# LMN_Danger_Shield-v18.net
KiCad netlist of a schematic drawn in EAGLE
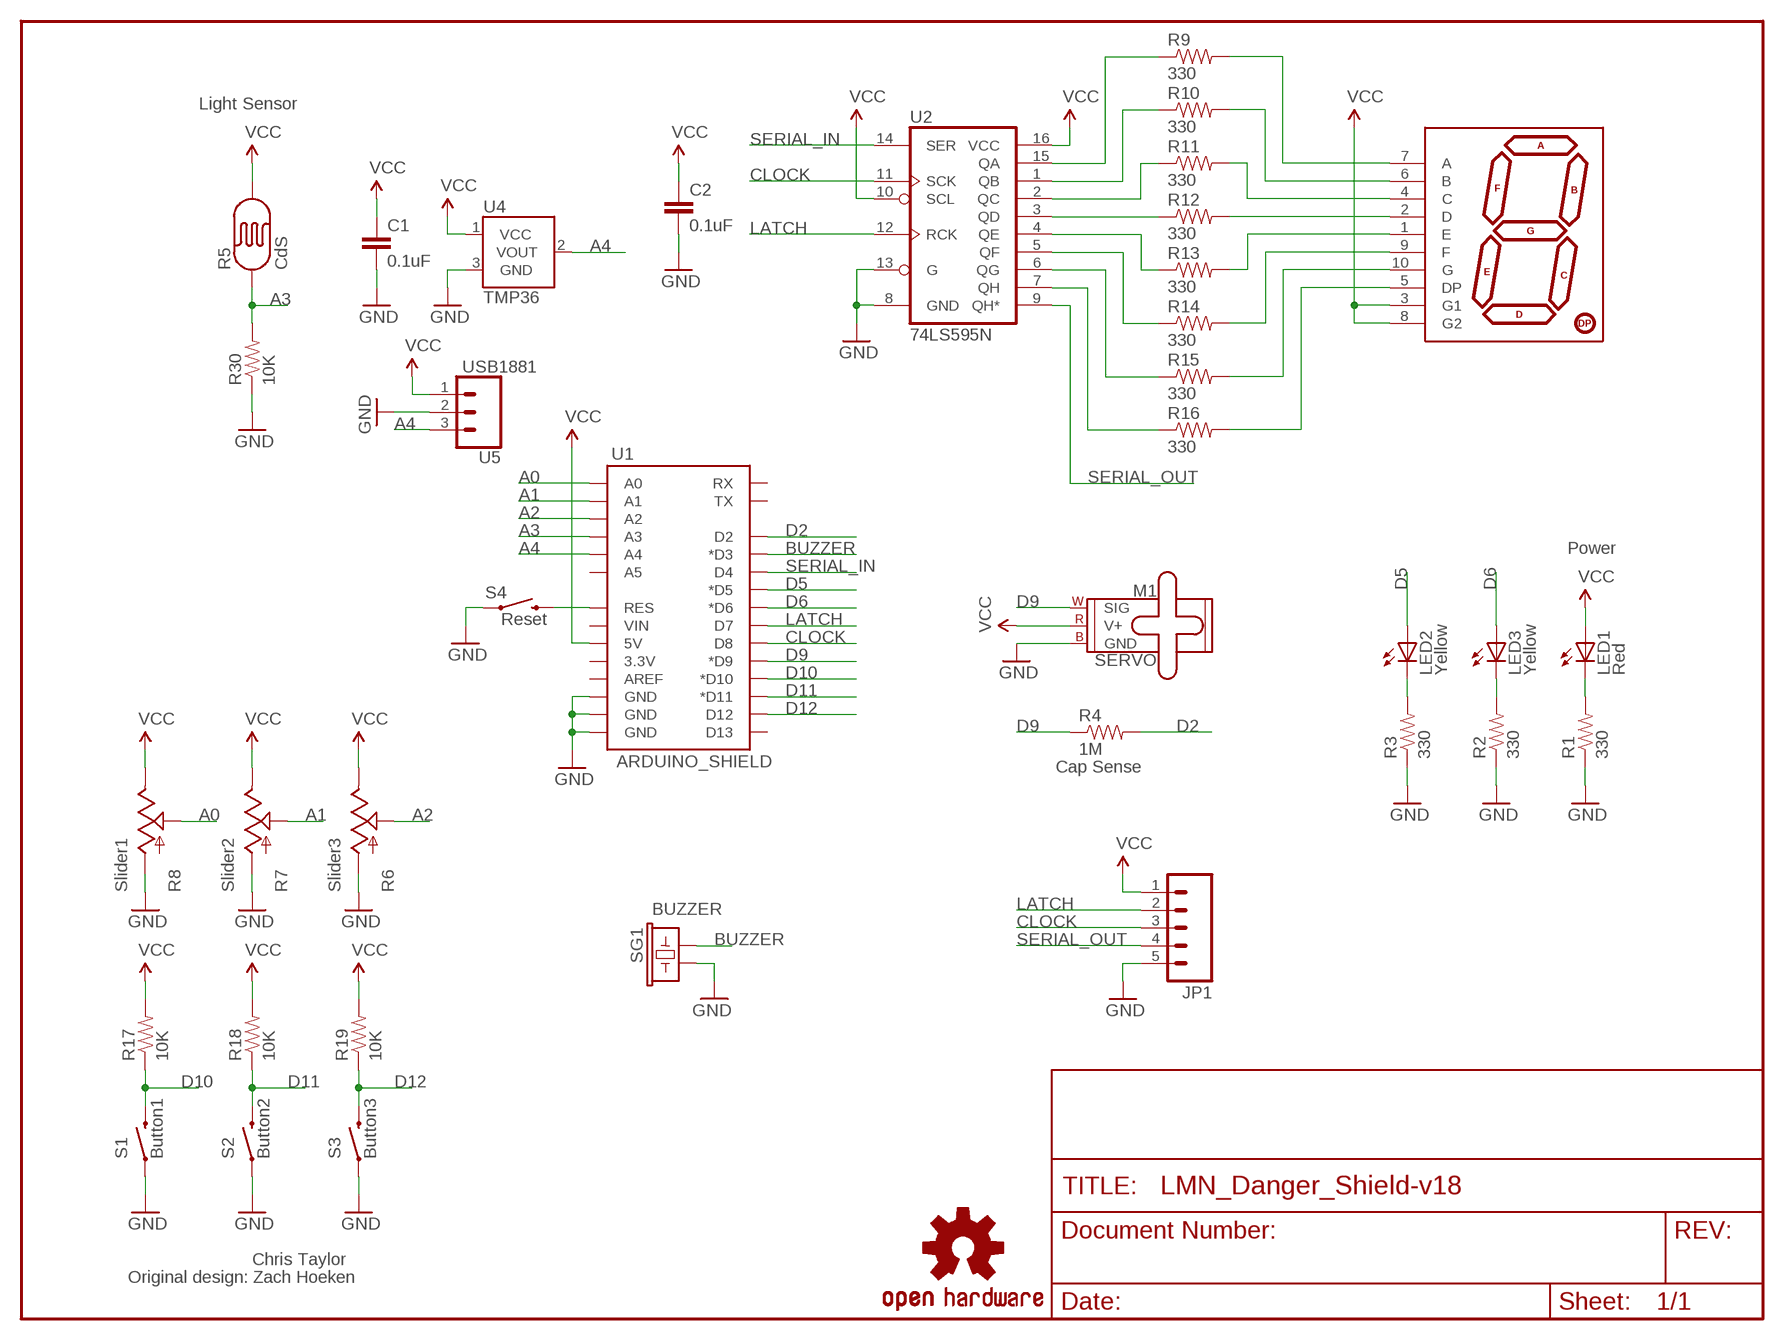
[diagram p0: schematic, sheet 1]

(export (version "E")
  (design (tool "Eeschema 10.0.6"))
  (components
    (comp (ref "C1")
      (value "0.1uF")
      (footprint "eagle-import:CAP-PTH-SMALL2")
      (libsource (lib "eagle-import") (part "CAPPTH2"))
    )
    (comp (ref "C2")
      (value "0.1uF")
      (footprint "eagle-import:CAP-PTH-SMALL2")
      (libsource (lib "eagle-import") (part "CAPPTH2"))
    )
    (comp (ref "JP1")
      (value "M05PTH")
      (footprint "eagle-import:1X05")
      (libsource (lib "eagle-import") (part "M05PTH"))
    )
    (comp (ref "LED1")
      (value "Red")
      (footprint "eagle-import:LED5MM")
      (libsource (lib "eagle-import") (part "LED5MM"))
    )
    (comp (ref "LED2")
      (value "Yellow")
      (footprint "eagle-import:LED5MM")
      (libsource (lib "eagle-import") (part "LED5MM"))
    )
    (comp (ref "LED3")
      (value "Yellow")
      (footprint "eagle-import:LED5MM")
      (libsource (lib "eagle-import") (part "LED5MM"))
    )
    (comp (ref "M1")
      (value "SERVO")
      (footprint "eagle-import:1X03")
      (libsource (lib "eagle-import") (part "SERVO"))
    )
    (comp (ref "R1")
      (value "330")
      (footprint "eagle-import:AXIAL-0.3")
      (libsource (lib "eagle-import") (part "RESISTORAXIAL-0.3"))
    )
    (comp (ref "R2")
      (value "330")
      (footprint "eagle-import:AXIAL-0.3")
      (libsource (lib "eagle-import") (part "RESISTORAXIAL-0.3"))
    )
    (comp (ref "R3")
      (value "330")
      (footprint "eagle-import:AXIAL-0.3")
      (libsource (lib "eagle-import") (part "RESISTORAXIAL-0.3"))
    )
    (comp (ref "R4")
      (value "1M")
      (footprint "eagle-import:AXIAL-0.3")
      (libsource (lib "eagle-import") (part "RESISTORAXIAL-0.3"))
    )
    (comp (ref "R5")
      (value "CdS")
      (footprint "eagle-import:PHOTOCELL")
      (libsource (lib "eagle-import") (part "PHOTOCELLPTH"))
    )
    (comp (ref "R6")
      (value "Slider3")
      (footprint "eagle-import:SLIDER")
      (libsource (lib "eagle-import") (part "SLIDER"))
    )
    (comp (ref "R7")
      (value "Slider2")
      (footprint "eagle-import:SLIDER")
      (libsource (lib "eagle-import") (part "SLIDER"))
    )
    (comp (ref "R8")
      (value "Slider1")
      (footprint "eagle-import:SLIDER")
      (libsource (lib "eagle-import") (part "SLIDER"))
    )
    (comp (ref "R9")
      (value "330")
      (footprint "eagle-import:AXIAL-0.3")
      (libsource (lib "eagle-import") (part "RESISTORAXIAL-0.3"))
    )
    (comp (ref "R10")
      (value "330")
      (footprint "eagle-import:AXIAL-0.3")
      (libsource (lib "eagle-import") (part "RESISTORAXIAL-0.3"))
    )
    (comp (ref "R11")
      (value "330")
      (footprint "eagle-import:AXIAL-0.3")
      (libsource (lib "eagle-import") (part "RESISTORAXIAL-0.3"))
    )
    (comp (ref "R12")
      (value "330")
      (footprint "eagle-import:AXIAL-0.3")
      (libsource (lib "eagle-import") (part "RESISTORAXIAL-0.3"))
    )
    (comp (ref "R13")
      (value "330")
      (footprint "eagle-import:AXIAL-0.3")
      (libsource (lib "eagle-import") (part "RESISTORAXIAL-0.3"))
    )
    (comp (ref "R14")
      (value "330")
      (footprint "eagle-import:AXIAL-0.3")
      (libsource (lib "eagle-import") (part "RESISTORAXIAL-0.3"))
    )
    (comp (ref "R15")
      (value "330")
      (footprint "eagle-import:AXIAL-0.3")
      (libsource (lib "eagle-import") (part "RESISTORAXIAL-0.3"))
    )
    (comp (ref "R16")
      (value "330")
      (footprint "eagle-import:AXIAL-0.3")
      (libsource (lib "eagle-import") (part "RESISTORAXIAL-0.3"))
    )
    (comp (ref "R17")
      (value "10K")
      (footprint "eagle-import:AXIAL-0.3")
      (libsource (lib "eagle-import") (part "RESISTORAXIAL-0.3"))
    )
    (comp (ref "R18")
      (value "10K")
      (footprint "eagle-import:AXIAL-0.3")
      (libsource (lib "eagle-import") (part "RESISTORAXIAL-0.3"))
    )
    (comp (ref "R19")
      (value "10K")
      (footprint "eagle-import:AXIAL-0.3")
      (libsource (lib "eagle-import") (part "RESISTORAXIAL-0.3"))
    )
    (comp (ref "R30")
      (value "10K")
      (footprint "eagle-import:AXIAL-0.3")
      (libsource (lib "eagle-import") (part "RESISTORAXIAL-0.3"))
    )
    (comp (ref "S1")
      (value "Button1")
      (footprint "eagle-import:TACTILE-PTH-12MM")
      (libsource (lib "eagle-import") (part "SWITCH-MOMENTARY-212MM"))
    )
    (comp (ref "S2")
      (value "Button2")
      (footprint "eagle-import:TACTILE-PTH-12MM")
      (libsource (lib "eagle-import") (part "SWITCH-MOMENTARY-212MM"))
    )
    (comp (ref "S3")
      (value "Button3")
      (footprint "eagle-import:TACTILE-PTH-12MM")
      (libsource (lib "eagle-import") (part "SWITCH-MOMENTARY-212MM"))
    )
    (comp (ref "S4")
      (value "Reset")
      (footprint "eagle-import:TACTILE-PTH")
      (libsource (lib "eagle-import") (part "SWITCH-MOMENTARY-2PTH"))
    )
    (comp (ref "SG1")
      (value "BUZZER")
      (footprint "eagle-import:BUZZER-12MM")
      (libsource (lib "eagle-import") (part "BUZZERPTH"))
    )
    (comp (ref "U$2")
      (value "OSHW-LOGOM")
      (footprint "eagle-import:OSHW-LOGO-M")
      (libsource (lib "eagle-import") (part "OSHW-LOGOM"))
    )
    (comp (ref "U1")
      (value "ARDUINO_SHIELD")
      (footprint "eagle-import:DUEMILANOVE_VIAS")
      (libsource (lib "eagle-import") (part "ARDUINO_SHIELDNO_SILK"))
    )
    (comp (ref "U2")
      (value "74LS595N")
      (footprint "eagle-import:DIL16")
      (libsource (lib "eagle-import") (part "74595NLS"))
    )
    (comp (ref "U4")
      (value "TMP36")
      (footprint "eagle-import:TO-92")
      (libsource (lib "eagle-import") (part "TMP36GT9"))
    )
    (comp (ref "U5")
      (value "USB1881")
      (footprint "eagle-import:1X03")
      (libsource (lib "eagle-import") (part "CONN_03"))
    )
    (comp (ref "U6")
      (value "7-SEGMENT-DISPLAY-1\"-RED")
      (footprint "eagle-import:7-SEGMENT-1_PTH")
      (libsource (lib "eagle-import") (part "7-SEGMENT-DISPLAY-1{dblquote}-RED"))
    )
  )
  (nets
    (net (code "1") (name "/A0") (class "Default")
      (node (ref "R8") (pin "2A") (pinfunction "S_2A") (pintype "passive"))
      (node (ref "U1") (pin "A0") (pinfunction "A0_A0") (pintype "bidirectional"))
    )
    (net (code "2") (name "/A1") (class "Default")
      (node (ref "R7") (pin "2A") (pinfunction "S_2A") (pintype "passive"))
      (node (ref "U1") (pin "A1") (pinfunction "A1_A1") (pintype "bidirectional"))
    )
    (net (code "3") (name "/A2") (class "Default")
      (node (ref "R6") (pin "2A") (pinfunction "S_2A") (pintype "passive"))
      (node (ref "U1") (pin "A2") (pinfunction "A2_A2") (pintype "bidirectional"))
    )
    (net (code "4") (name "/A3") (class "Default")
      (node (ref "R30") (pin "P$2") (pinfunction "2_P$2") (pintype "passive"))
      (node (ref "R5") (pin "1") (pinfunction "P$1_1") (pintype "bidirectional"))
      (node (ref "U1") (pin "A3") (pinfunction "A3_A3") (pintype "bidirectional"))
    )
    (net (code "5") (name "/A4") (class "Default")
      (node (ref "U1") (pin "A4") (pinfunction "A4_A4") (pintype "bidirectional"))
      (node (ref "U4") (pin "2") (pinfunction "VOUT_2") (pintype "bidirectional"))
      (node (ref "U5") (pin "3") (pinfunction "3_3") (pintype "passive"))
    )
    (net (code "6") (name "/BUZZER") (class "Default")
      (node (ref "SG1") (pin "+") (pinfunction "1_+") (pintype "passive"))
      (node (ref "U1") (pin "D3") (pinfunction "*D3_D3") (pintype "bidirectional"))
    )
    (net (code "7") (name "/CLOCK") (class "Default")
      (node (ref "JP1") (pin "3") (pinfunction "3_3") (pintype "passive"))
      (node (ref "U1") (pin "D8") (pinfunction "D8_D8") (pintype "bidirectional"))
      (node (ref "U2") (pin "11") (pinfunction "SCK_11") (pintype "input"))
    )
    (net (code "8") (name "/D2") (class "Default")
      (node (ref "R4") (pin "P$2") (pinfunction "2_P$2") (pintype "passive"))
      (node (ref "U1") (pin "D2") (pinfunction "D2_D2") (pintype "bidirectional"))
    )
    (net (code "9") (name "/D5") (class "Default")
      (node (ref "LED2") (pin "A") (pinfunction "A_A") (pintype "passive"))
      (node (ref "U1") (pin "D5") (pinfunction "*D5_D5") (pintype "bidirectional"))
    )
    (net (code "10") (name "/D6") (class "Default")
      (node (ref "LED3") (pin "A") (pinfunction "A_A") (pintype "passive"))
      (node (ref "U1") (pin "D6") (pinfunction "*D6_D6") (pintype "bidirectional"))
    )
    (net (code "11") (name "/D9") (class "Default")
      (node (ref "M1") (pin "1") (pinfunction "SIG_1") (pintype "bidirectional"))
      (node (ref "R4") (pin "P$1") (pinfunction "1_P$1") (pintype "passive"))
      (node (ref "U1") (pin "D9") (pinfunction "*D9_D9") (pintype "bidirectional"))
    )
    (net (code "12") (name "/D10") (class "Default")
      (node (ref "R17") (pin "P$1") (pinfunction "1_P$1") (pintype "passive"))
      (node (ref "S1") (pin "3") (pinfunction "2_3") (pintype "passive"))
      (node (ref "U1") (pin "D10") (pinfunction "*D10_D10") (pintype "bidirectional"))
    )
    (net (code "13") (name "/D11") (class "Default")
      (node (ref "R18") (pin "P$1") (pinfunction "1_P$1") (pintype "passive"))
      (node (ref "S2") (pin "3") (pinfunction "2_3") (pintype "passive"))
      (node (ref "U1") (pin "D11") (pinfunction "*D11_D11") (pintype "bidirectional"))
    )
    (net (code "14") (name "/D12") (class "Default")
      (node (ref "R19") (pin "P$1") (pinfunction "1_P$1") (pintype "passive"))
      (node (ref "S3") (pin "3") (pinfunction "2_3") (pintype "passive"))
      (node (ref "U1") (pin "D12") (pinfunction "D12_D12") (pintype "bidirectional"))
    )
    (net (code "15") (name "/LATCH") (class "Default")
      (node (ref "JP1") (pin "2") (pinfunction "2_2") (pintype "passive"))
      (node (ref "U1") (pin "D7") (pinfunction "D7_D7") (pintype "bidirectional"))
      (node (ref "U2") (pin "12") (pinfunction "RCK_12") (pintype "input"))
    )
    (net (code "16") (name "/SERIAL_IN") (class "Default")
      (node (ref "U1") (pin "D4") (pinfunction "D4_D4") (pintype "bidirectional"))
      (node (ref "U2") (pin "14") (pinfunction "SER_14") (pintype "input"))
    )
    (net (code "17") (name "/SERIAL_OUT") (class "Default")
      (node (ref "JP1") (pin "4") (pinfunction "4_4") (pintype "passive"))
      (node (ref "U2") (pin "9") (pinfunction "QH*_9") (pintype "tri_state"))
    )
    (net (code "18") (name "GND") (class "Default")
      (node (ref "C1") (pin "2") (pinfunction "2_2") (pintype "passive"))
      (node (ref "C2") (pin "2") (pinfunction "2_2") (pintype "passive"))
      (node (ref "JP1") (pin "5") (pinfunction "5_5") (pintype "passive"))
      (node (ref "M1") (pin "3") (pinfunction "GND_3") (pintype "bidirectional"))
      (node (ref "R1") (pin "P$1") (pinfunction "1_P$1") (pintype "passive"))
      (node (ref "R2") (pin "P$1") (pinfunction "1_P$1") (pintype "passive"))
      (node (ref "R3") (pin "P$1") (pinfunction "1_P$1") (pintype "passive"))
      (node (ref "R30") (pin "P$1") (pinfunction "1_P$1") (pintype "passive"))
      (node (ref "R6") (pin "3") (pinfunction "A_3") (pintype "passive"))
      (node (ref "R7") (pin "3") (pinfunction "A_3") (pintype "passive"))
      (node (ref "R8") (pin "3") (pinfunction "A_3") (pintype "passive"))
      (node (ref "S1") (pin "1") (pinfunction "1_1") (pintype "passive"))
      (node (ref "S2") (pin "1") (pinfunction "1_1") (pintype "passive"))
      (node (ref "S3") (pin "1") (pinfunction "1_1") (pintype "passive"))
      (node (ref "S4") (pin "1") (pinfunction "1_1") (pintype "passive"))
      (node (ref "SG1") (pin "-") (pinfunction "2_-") (pintype "passive"))
      (node (ref "U1") (pin "GND@0") (pinfunction "GND_GND@0") (pintype "bidirectional"))
      (node (ref "U1") (pin "GND@1") (pinfunction "GND_GND@1") (pintype "bidirectional"))
      (node (ref "U1") (pin "GND@2") (pinfunction "GND_GND@2") (pintype "bidirectional"))
      (node (ref "U2") (pin "13") (pinfunction "G_13") (pintype "input"))
      (node (ref "U2") (pin "8") (pinfunction "GND_8") (pintype "power_in"))
      (node (ref "U4") (pin "3") (pinfunction "GND_3") (pintype "bidirectional"))
      (node (ref "U5") (pin "2") (pinfunction "2_2") (pintype "passive"))
    )
    (net (code "19") (name "Net-(LED1-C)") (class "Default")
      (node (ref "LED1") (pin "K") (pinfunction "C_K") (pintype "passive"))
      (node (ref "R1") (pin "P$2") (pinfunction "2_P$2") (pintype "passive"))
    )
    (net (code "20") (name "Net-(LED2-C)") (class "Default")
      (node (ref "LED2") (pin "K") (pinfunction "C_K") (pintype "passive"))
      (node (ref "R3") (pin "P$2") (pinfunction "2_P$2") (pintype "passive"))
    )
    (net (code "21") (name "Net-(LED3-C)") (class "Default")
      (node (ref "LED3") (pin "K") (pinfunction "C_K") (pintype "passive"))
      (node (ref "R2") (pin "P$2") (pinfunction "2_P$2") (pintype "passive"))
    )
    (net (code "22") (name "Net-(R9-1)") (class "Default")
      (node (ref "R9") (pin "P$1") (pinfunction "1_P$1") (pintype "passive"))
      (node (ref "U2") (pin "15") (pinfunction "QA_15") (pintype "tri_state"))
    )
    (net (code "23") (name "Net-(R9-2)") (class "Default")
      (node (ref "R9") (pin "P$2") (pinfunction "2_P$2") (pintype "passive"))
      (node (ref "U6") (pin "7") (pinfunction "A_7") (pintype "bidirectional"))
    )
    (net (code "24") (name "Net-(R10-1)") (class "Default")
      (node (ref "R10") (pin "P$1") (pinfunction "1_P$1") (pintype "passive"))
      (node (ref "U2") (pin "1") (pinfunction "QB_1") (pintype "tri_state"))
    )
    (net (code "25") (name "Net-(R10-2)") (class "Default")
      (node (ref "R10") (pin "P$2") (pinfunction "2_P$2") (pintype "passive"))
      (node (ref "U6") (pin "6") (pinfunction "B_6") (pintype "bidirectional"))
    )
    (net (code "26") (name "Net-(R11-1)") (class "Default")
      (node (ref "R11") (pin "P$1") (pinfunction "1_P$1") (pintype "passive"))
      (node (ref "U2") (pin "2") (pinfunction "QC_2") (pintype "tri_state"))
    )
    (net (code "27") (name "Net-(R11-2)") (class "Default")
      (node (ref "R11") (pin "P$2") (pinfunction "2_P$2") (pintype "passive"))
      (node (ref "U6") (pin "4") (pinfunction "C_4") (pintype "bidirectional"))
    )
    (net (code "28") (name "Net-(R12-1)") (class "Default")
      (node (ref "R12") (pin "P$1") (pinfunction "1_P$1") (pintype "passive"))
      (node (ref "U2") (pin "3") (pinfunction "QD_3") (pintype "tri_state"))
    )
    (net (code "29") (name "Net-(R12-2)") (class "Default")
      (node (ref "R12") (pin "P$2") (pinfunction "2_P$2") (pintype "passive"))
      (node (ref "U6") (pin "2") (pinfunction "D_2") (pintype "bidirectional"))
    )
    (net (code "30") (name "Net-(R13-1)") (class "Default")
      (node (ref "R13") (pin "P$1") (pinfunction "1_P$1") (pintype "passive"))
      (node (ref "U2") (pin "4") (pinfunction "QE_4") (pintype "tri_state"))
    )
    (net (code "31") (name "Net-(R13-2)") (class "Default")
      (node (ref "R13") (pin "P$2") (pinfunction "2_P$2") (pintype "passive"))
      (node (ref "U6") (pin "1") (pinfunction "E_1") (pintype "bidirectional"))
    )
    (net (code "32") (name "Net-(R14-1)") (class "Default")
      (node (ref "R14") (pin "P$1") (pinfunction "1_P$1") (pintype "passive"))
      (node (ref "U2") (pin "5") (pinfunction "QF_5") (pintype "tri_state"))
    )
    (net (code "33") (name "Net-(R14-2)") (class "Default")
      (node (ref "R14") (pin "P$2") (pinfunction "2_P$2") (pintype "passive"))
      (node (ref "U6") (pin "9") (pinfunction "F_9") (pintype "bidirectional"))
    )
    (net (code "34") (name "Net-(R15-1)") (class "Default")
      (node (ref "R15") (pin "P$1") (pinfunction "1_P$1") (pintype "passive"))
      (node (ref "U2") (pin "6") (pinfunction "QG_6") (pintype "tri_state"))
    )
    (net (code "35") (name "Net-(R15-2)") (class "Default")
      (node (ref "R15") (pin "P$2") (pinfunction "2_P$2") (pintype "passive"))
      (node (ref "U6") (pin "10") (pinfunction "G_10") (pintype "bidirectional"))
    )
    (net (code "36") (name "Net-(R16-1)") (class "Default")
      (node (ref "R16") (pin "P$1") (pinfunction "1_P$1") (pintype "passive"))
      (node (ref "U2") (pin "7") (pinfunction "QH_7") (pintype "tri_state"))
    )
    (net (code "37") (name "Net-(R16-2)") (class "Default")
      (node (ref "R16") (pin "P$2") (pinfunction "2_P$2") (pintype "passive"))
      (node (ref "U6") (pin "5") (pinfunction "DP_5") (pintype "bidirectional"))
    )
    (net (code "38") (name "Net-(S4-2)") (class "Default")
      (node (ref "S4") (pin "3") (pinfunction "2_3") (pintype "passive"))
      (node (ref "U1") (pin "RES") (pinfunction "RES_RES") (pintype "bidirectional"))
    )
    (net (code "39") (name "VCC") (class "Default")
      (node (ref "C1") (pin "1") (pinfunction "1_1") (pintype "passive"))
      (node (ref "C2") (pin "1") (pinfunction "1_1") (pintype "passive"))
      (node (ref "JP1") (pin "1") (pinfunction "1_1") (pintype "passive"))
      (node (ref "LED1") (pin "A") (pinfunction "A_A") (pintype "passive"))
      (node (ref "M1") (pin "2") (pinfunction "V+_2") (pintype "bidirectional"))
      (node (ref "R17") (pin "P$2") (pinfunction "2_P$2") (pintype "passive"))
      (node (ref "R18") (pin "P$2") (pinfunction "2_P$2") (pintype "passive"))
      (node (ref "R19") (pin "P$2") (pinfunction "2_P$2") (pintype "passive"))
      (node (ref "R5") (pin "2") (pinfunction "P$2_2") (pintype "bidirectional"))
      (node (ref "R6") (pin "1") (pinfunction "E_1") (pintype "passive"))
      (node (ref "R7") (pin "1") (pinfunction "E_1") (pintype "passive"))
      (node (ref "R8") (pin "1") (pinfunction "E_1") (pintype "passive"))
      (node (ref "U1") (pin "5V") (pinfunction "5V_5V") (pintype "bidirectional"))
      (node (ref "U2") (pin "10") (pinfunction "SCL_10") (pintype "input"))
      (node (ref "U2") (pin "16") (pinfunction "VCC_16") (pintype "power_in"))
      (node (ref "U4") (pin "1") (pinfunction "VCC_1") (pintype "bidirectional"))
      (node (ref "U5") (pin "1") (pinfunction "1_1") (pintype "passive"))
      (node (ref "U6") (pin "3") (pinfunction "G1_3") (pintype "bidirectional"))
      (node (ref "U6") (pin "8") (pinfunction "G2_8") (pintype "bidirectional"))
    )
    (net (code "40") (name "unconnected-(U1-Pad3.3V)") (class "Default")
      (node (ref "U1") (pin "3.3V") (pinfunction "3.3V_3.3V") (pintype "bidirectional"))
    )
    (net (code "41") (name "unconnected-(U1-PadA5)") (class "Default")
      (node (ref "U1") (pin "A5") (pinfunction "A5_A5") (pintype "bidirectional"))
    )
    (net (code "42") (name "unconnected-(U1-PadAREF)") (class "Default")
      (node (ref "U1") (pin "AREF") (pinfunction "AREF_AREF") (pintype "bidirectional"))
    )
    (net (code "43") (name "unconnected-(U1-PadD13)") (class "Default")
      (node (ref "U1") (pin "D13") (pinfunction "D13_D13") (pintype "bidirectional"))
    )
    (net (code "44") (name "unconnected-(U1-PadRX)") (class "Default")
      (node (ref "U1") (pin "RX") (pinfunction "RX_RX") (pintype "bidirectional"))
    )
    (net (code "45") (name "unconnected-(U1-PadTX)") (class "Default")
      (node (ref "U1") (pin "TX") (pinfunction "TX_TX") (pintype "bidirectional"))
    )
    (net (code "46") (name "unconnected-(U1-PadVIN)") (class "Default")
      (node (ref "U1") (pin "VIN") (pinfunction "VIN_VIN") (pintype "bidirectional"))
    )
  )
)
